# MCU.net
KiCad netlist of a schematic drawn in Altium Designer
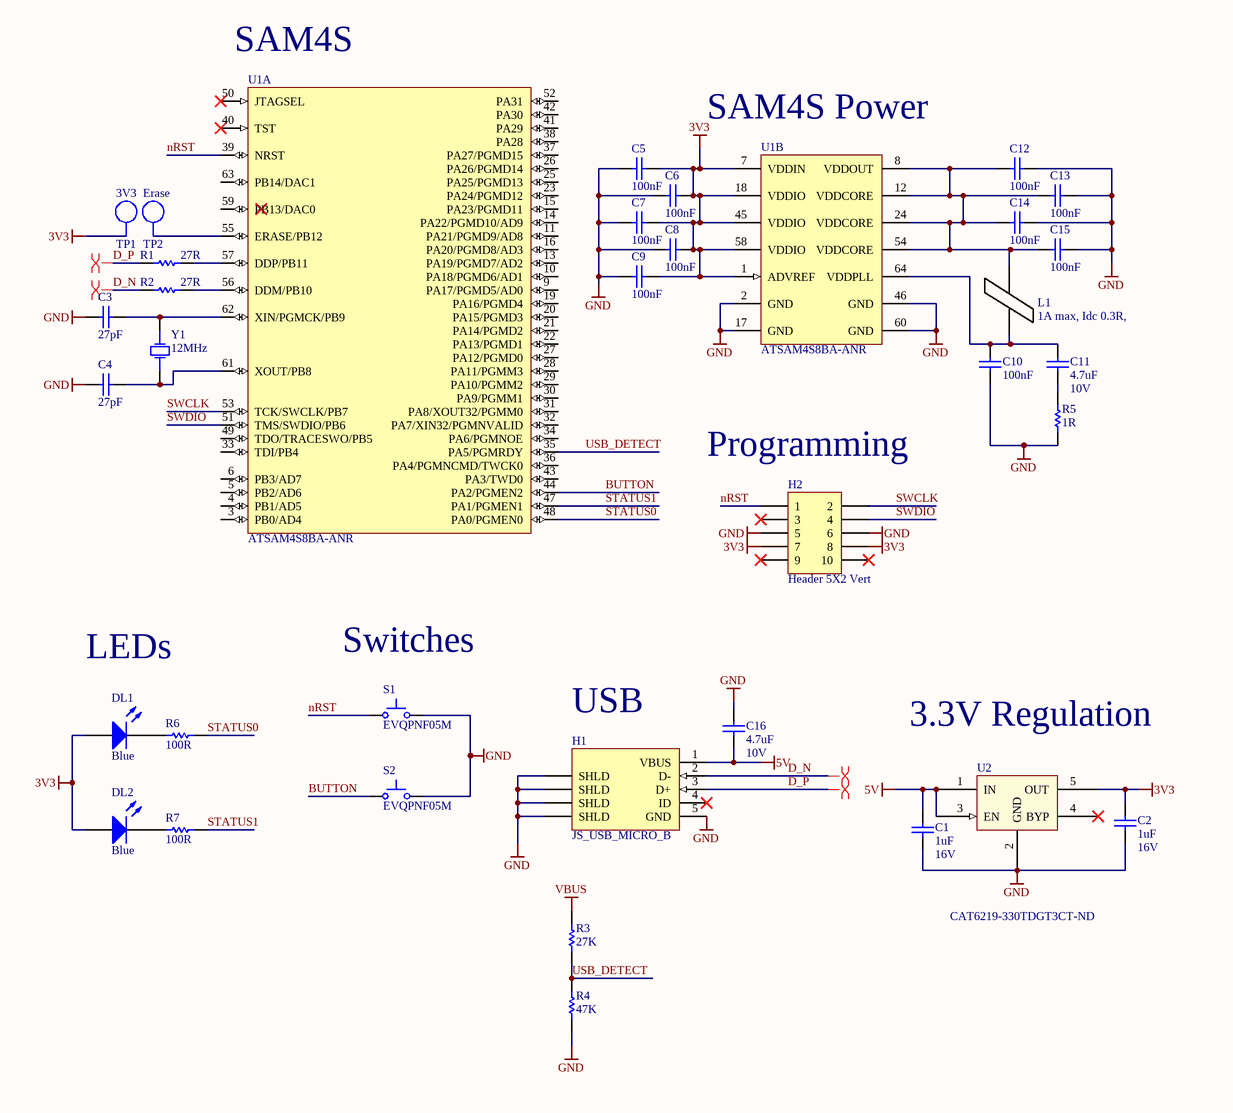
[diagram p0: MCU.SchDoc]

(export (version "E")
  (design (tool "Eeschema 10.0.6"))
  (components
    (comp (ref "C1")
      (value "1uF")
      (footprint "CAPC1608L")
      (description "CAP CER 1uF Y5V -20% +80% 16V 0603")
      (fields (field (name "MAX VOLTAGE") "16V"))
      (libsource (lib "ECE AD19Components_19V1") (part "CC_1uF_0603"))
    )
    (comp (ref "C2")
      (value "1uF")
      (footprint "CAPC1608L")
      (description "CAP CER 1uF Y5V -20% +80% 16V 0603")
      (fields (field (name "MAX VOLTAGE") "16V"))
      (libsource (lib "ECE AD19Components_19V1") (part "CC_1uF_0603"))
    )
    (comp (ref "C3")
      (value "27pF")
      (footprint "CAPC1608L")
      (description "CAP CER 27pF NPO/COG +-5% 50V 0603")
      (libsource (lib "ECE AD19Components_19V1") (part "CC_27pF_0603"))
    )
    (comp (ref "C4")
      (value "27pF")
      (footprint "CAPC1608L")
      (description "CAP CER 27pF NPO/COG +-5% 50V 0603")
      (libsource (lib "ECE AD19Components_19V1") (part "CC_27pF_0603"))
    )
    (comp (ref "C5")
      (value "100nF")
      (footprint "CAPC1608L")
      (description "CAP CER 100nF X7R +-10% 50V 0603")
      (libsource (lib "ECE AD19Components_19V1") (part "CC_100nF_0603"))
    )
    (comp (ref "C6")
      (value "100nF")
      (footprint "CAPC1608L")
      (description "CAP CER 100nF X7R +-10% 50V 0603")
      (libsource (lib "ECE AD19Components_19V1") (part "CC_100nF_0603"))
    )
    (comp (ref "C7")
      (value "100nF")
      (footprint "CAPC1608L")
      (description "CAP CER 100nF X7R +-10% 50V 0603")
      (libsource (lib "ECE AD19Components_19V1") (part "CC_100nF_0603"))
    )
    (comp (ref "C8")
      (value "100nF")
      (footprint "CAPC1608L")
      (description "CAP CER 100nF X7R +-10% 50V 0603")
      (libsource (lib "ECE AD19Components_19V1") (part "CC_100nF_0603"))
    )
    (comp (ref "C9")
      (value "100nF")
      (footprint "CAPC1608L")
      (description "CAP CER 100nF X7R +-10% 50V 0603")
      (libsource (lib "ECE AD19Components_19V1") (part "CC_100nF_0603"))
    )
    (comp (ref "C10")
      (value "100nF")
      (footprint "CAPC1608L")
      (description "CAP CER 100nF X7R +-10% 50V 0603")
      (libsource (lib "ECE AD19Components_19V1") (part "CC_100nF_0603"))
    )
    (comp (ref "C11")
      (value "4.7uF")
      (footprint "CAPC1608N")
      (description "CAP CER 4.7uF X5R +-20%  10V 0603")
      (fields (field (name "MAX VOLTAGE") "10V"))
      (libsource (lib "ECE AD19Components_19V1") (part "CC_4.7uF_0603"))
    )
    (comp (ref "C12")
      (value "100nF")
      (footprint "CAPC1608L")
      (description "CAP CER 100nF X7R +-10% 50V 0603")
      (libsource (lib "ECE AD19Components_19V1") (part "CC_100nF_0603"))
    )
    (comp (ref "C13")
      (value "100nF")
      (footprint "CAPC1608L")
      (description "CAP CER 100nF X7R +-10% 50V 0603")
      (libsource (lib "ECE AD19Components_19V1") (part "CC_100nF_0603"))
    )
    (comp (ref "C14")
      (value "100nF")
      (footprint "CAPC1608L")
      (description "CAP CER 100nF X7R +-10% 50V 0603")
      (libsource (lib "ECE AD19Components_19V1") (part "CC_100nF_0603"))
    )
    (comp (ref "C15")
      (value "100nF")
      (footprint "CAPC1608L")
      (description "CAP CER 100nF X7R +-10% 50V 0603")
      (libsource (lib "ECE AD19Components_19V1") (part "CC_100nF_0603"))
    )
    (comp (ref "C16")
      (value "4.7uF")
      (footprint "CAPC1608N")
      (description "CAP CER 4.7uF X5R +-20%  10V 0603")
      (fields (field (name "MAX VOLTAGE") "10V"))
      (libsource (lib "ECE AD19Components_19V1") (part "CC_4.7uF_0603"))
    )
    (comp (ref "DL1")
      (value "Blue")
      (footprint "WL-SMCW0603")
      (description "LED Blue 270mcd 0603 SMD")
      (fields
        (field (name "MANUFACTURER") "WURTH ELEKTRONIK")
        (field (name "MANUFACTURER PART NUMBER") "150060BS75000")
        (field (name "LED COLOUR") "Blue")
      )
      (libsource (lib "ECE AD19Components_19V1") (part "DL_150060BS75000"))
    )
    (comp (ref "DL2")
      (value "Blue")
      (footprint "WL-SMCW0603")
      (description "LED Blue 270mcd 0603 SMD")
      (fields
        (field (name "MANUFACTURER") "WURTH ELEKTRONIK")
        (field (name "MANUFACTURER PART NUMBER") "150060BS75000")
        (field (name "LED COLOUR") "Blue")
      )
      (libsource (lib "ECE AD19Components_19V1") (part "DL_150060BS75000"))
    )
    (comp (ref "H1")
      (value "JS_USB_MICRO_B")
      (footprint "FCI_USB_10118194-0001LF")
      (description "CONN USB MICRO B RECPT SMT R/A")
      (fields (field (name "MANUFACTURER") "FCI") (field (name "MANUFACTURER PART NUMBER") "10118194-0001LF"))
      (libsource (lib "ECE AD19Components_19V1") (part "JS_USB_MICRO_B_SMT"))
    )
    (comp (ref "H2")
      (value "Header 5X2 Vert")
      (footprint "IDC2.54-V10D")
      (description "IDC Header, 2,54mm, 10-Pin, Vert")
      (libsource (lib "ECE AD19Components_19V1") (part "JA_HDR_IDC_5X2_VERT"))
    )
    (comp (ref "L1")
      (value "1A max, Idc 0.3R,")
      (footprint "INDC3216L")
      (description "Ferrite Bead, Rdc 0.3R, Z100MHZ 600R, Imax 1A, SMD 1206")
      (fields
        (field (name "MANUFACTURER") "FAIR-RITE")
        (field (name "MANUFACTURER PART NUMBER") "2512066017Y1")
      )
      (libsource (lib "ECE AD19Components_19V1") (part "IN_Ferrite-Bead"))
    )
    (comp (ref "R1")
      (value "27R")
      (footprint "RESC3216L")
      (description "RES 27R OHM 1/4W 5% 1206 SMD")
      (libsource (lib "ECE AD19Components_19V1") (part "RT_27R"))
    )
    (comp (ref "R2")
      (value "27R")
      (footprint "RESC3216L")
      (description "RES 27R OHM 1/4W 5% 1206 SMD")
      (libsource (lib "ECE AD19Components_19V1") (part "RT_27R"))
    )
    (comp (ref "R3")
      (value "27K")
      (footprint "RESC1608L")
      (description "RES 27K OHM 1/10W 5% 0603 SMD")
      (libsource (lib "ECE AD19Components_19V1") (part "RS_27K"))
    )
    (comp (ref "R4")
      (value "47K")
      (footprint "RESC1608L")
      (description "RES 27K OHM 1/10W 5% 0603 SMD")
      (libsource (lib "ECE AD19Components_19V1") (part "RS_27K"))
    )
    (comp (ref "R5")
      (value "1R")
      (footprint "RESC3216L")
      (description "RES 1R OHM 1/4W 5% 1206 SMD")
      (libsource (lib "ECE AD19Components_19V1") (part "RT_1R"))
    )
    (comp (ref "R6")
      (value "100R")
      (footprint "RESC3216L")
      (description "RES 100R OHM 1/4W 5% 1206 SMD")
      (libsource (lib "ECE AD19Components_19V1") (part "RT_100R"))
    )
    (comp (ref "R7")
      (value "100R")
      (footprint "RESC3216L")
      (description "RES 100R OHM 1/4W 5% 1206 SMD")
      (libsource (lib "ECE AD19Components_19V1") (part "RT_100R"))
    )
    (comp (ref "S1")
      (value "EVQPNF05M")
      (footprint "EVQPNF05M")
      (description "Panasonic 6 x 3.5mm SMD Light Touch Switch Type SMD")
      (fields (field (name "MANUFACTURER") "Panasonic"))
      (libsource (lib "ECE AD19Components_19V1") (part "WS_EVQPNF05M"))
    )
    (comp (ref "S2")
      (value "EVQPNF05M")
      (footprint "EVQPNF05M")
      (description "Panasonic 6 x 3.5mm SMD Light Touch Switch Type SMD")
      (fields (field (name "MANUFACTURER") "Panasonic"))
      (libsource (lib "ECE AD19Components_19V1") (part "WS_EVQPNF05M"))
    )
    (comp (ref "TP1")
      (value "3V3")
      (footprint "TP_1206")
      (description "Test-Point 3.3x1.6x2.1mm SMD")
      (fields
        (field (name "MANUFACTURER") "Harwin Inc")
        (field (name "MANUFACTURER PART NUMBER") "S1751-46R")
      )
      (libsource (lib "ECE AD19Components_19V1") (part "TP_1206"))
    )
    (comp (ref "TP2")
      (value "Erase")
      (footprint "TP_1206")
      (description "Test-Point 3.3x1.6x2.1mm SMD")
      (fields
        (field (name "MANUFACTURER") "Harwin Inc")
        (field (name "MANUFACTURER PART NUMBER") "S1751-46R")
      )
      (libsource (lib "ECE AD19Components_19V1") (part "TP_1206"))
    )
    (comp (ref "U1")
      (value "ATSAM4S8BA-ANR")
      (footprint "LQFP64_L")
      (description "IC MCU 32BIT 512KB FLASH 64LQFP")
      (fields (field (name "MANUFACTURER") "Atmel"))
      (libsource (lib "ECE AD19Components_19V1") (part "SE_ATSAM4S16BA-MU"))
    )
    (comp (ref "U2")
      (value "CAT6219-330TDGT3")
      (footprint "SOT95P280X145-5N")
      (description "IC REG LIN 3.3V 500MA TSOT23-5")
      (fields
        (field (name "BASE PART NUMBER") "CAT6219")
        (field (name "SUPPLIER PART NUMBER") "CAT6219-330TDGT3CT-ND")
      )
      (libsource (lib "ENCE461AD19_19V2") (part "SV_CAT6219-330TDGT3"))
    )
    (comp (ref "Y1")
      (value "12MHz")
      (footprint "6.0X3.5-4")
      (description "CRYSTAL 12MHZ 18PF 6X3.5mm SMD")
      (fields
        (field (name "MANUFACTURER") "CTS-Frequency Controls")
        (field (name "MANUFACTURER PART NUMBER") "406C35D12M00000")
        (field (name "FREQUENCY") "12MHz")
      )
      (libsource (lib "ECE AD19Components_19V1") (part "XT_CRYSTAL_12MHz_18pF"))
    )
  )
  (nets
    (net (code "1") (name "/BUTTON") (class "Default")
      (node (ref "S2") (pin "1") (pintype "passive"))
      (node (ref "U1") (pin "44") (pinfunction "PA2/PGMEN2_44") (pintype "bidirectional"))
    )
    (net (code "2") (name "/D_N") (class "Default")
      (node (ref "H1") (pin "2") (pinfunction "D-_2") (pintype "input"))
      (node (ref "R2") (pin "1") (pinfunction "1_1") (pintype "passive"))
    )
    (net (code "3") (name "/D_P") (class "Default")
      (node (ref "H1") (pin "3") (pinfunction "D+_3") (pintype "input"))
      (node (ref "R1") (pin "1") (pinfunction "1_1") (pintype "passive"))
    )
    (net (code "4") (name "/STATUS0") (class "Default")
      (node (ref "R6") (pin "2") (pinfunction "2_2") (pintype "passive"))
      (node (ref "U1") (pin "48") (pinfunction "PA0/PGMEN0_48") (pintype "bidirectional"))
    )
    (net (code "5") (name "/STATUS1") (class "Default")
      (node (ref "R7") (pin "2") (pinfunction "2_2") (pintype "passive"))
      (node (ref "U1") (pin "47") (pinfunction "PA1/PGMEN1_47") (pintype "bidirectional"))
    )
    (net (code "6") (name "/SWCLK") (class "Default")
      (node (ref "H2") (pin "2") (pinfunction "2_2") (pintype "passive"))
      (node (ref "U1") (pin "53") (pinfunction "TCK/SWCLK/PB7_53") (pintype "bidirectional"))
    )
    (net (code "7") (name "/SWDIO") (class "Default")
      (node (ref "H2") (pin "4") (pinfunction "4_4") (pintype "passive"))
      (node (ref "U1") (pin "51") (pinfunction "TMS/SWDIO/PB6_51") (pintype "bidirectional"))
    )
    (net (code "8") (name "/USB_DETECT") (class "Default")
      (node (ref "R3") (pin "1") (pinfunction "1_1") (pintype "passive"))
      (node (ref "R4") (pin "2") (pinfunction "2_2") (pintype "passive"))
      (node (ref "U1") (pin "35") (pinfunction "PA5/PGMRDY_35") (pintype "bidirectional"))
    )
    (net (code "9") (name "/nRST") (class "Default")
      (node (ref "H2") (pin "1") (pinfunction "1_1") (pintype "passive"))
      (node (ref "S1") (pin "1") (pintype "passive"))
      (node (ref "U1") (pin "39") (pinfunction "NRST_39") (pintype "bidirectional"))
    )
    (net (code "10") (name "3V3") (class "Default")
      (node (ref "C2") (pin "2") (pinfunction "2_2") (pintype "passive"))
      (node (ref "C5") (pin "2") (pinfunction "2_2") (pintype "passive"))
      (node (ref "C6") (pin "2") (pinfunction "2_2") (pintype "passive"))
      (node (ref "C7") (pin "2") (pinfunction "2_2") (pintype "passive"))
      (node (ref "C8") (pin "2") (pinfunction "2_2") (pintype "passive"))
      (node (ref "C9") (pin "2") (pinfunction "2_2") (pintype "passive"))
      (node (ref "DL1") (pin "2") (pinfunction "A_2") (pintype "passive"))
      (node (ref "DL2") (pin "2") (pinfunction "A_2") (pintype "passive"))
      (node (ref "H2") (pin "7") (pinfunction "7_7") (pintype "passive"))
      (node (ref "H2") (pin "8") (pinfunction "8_8") (pintype "passive"))
      (node (ref "TP1") (pin "1") (pinfunction "1_1") (pintype "passive"))
      (node (ref "U1") (pin "1") (pinfunction "ADVREF_1") (pintype "input"))
      (node (ref "U1") (pin "18") (pinfunction "VDDIO_18") (pintype "power_in"))
      (node (ref "U1") (pin "45") (pinfunction "VDDIO_45") (pintype "power_in"))
      (node (ref "U1") (pin "58") (pinfunction "VDDIO_58") (pintype "power_in"))
      (node (ref "U1") (pin "7") (pinfunction "VDDIN_7") (pintype "power_in"))
      (node (ref "U2") (pin "5") (pinfunction "OUT_5") (pintype "power_in"))
    )
    (net (code "11") (name "5V") (class "Default")
      (node (ref "C1") (pin "2") (pinfunction "2_2") (pintype "passive"))
      (node (ref "C16") (pin "1") (pinfunction "1_1") (pintype "passive"))
      (node (ref "H1") (pin "1") (pinfunction "VBUS_1") (pintype "power_in"))
      (node (ref "U2") (pin "1") (pinfunction "IN_1") (pintype "power_in"))
      (node (ref "U2") (pin "3") (pinfunction "EN_3") (pintype "input"))
    )
    (net (code "12") (name "GND") (class "Default")
      (node (ref "C1") (pin "1") (pinfunction "1_1") (pintype "passive"))
      (node (ref "C10") (pin "1") (pinfunction "1_1") (pintype "passive"))
      (node (ref "C12") (pin "2") (pinfunction "2_2") (pintype "passive"))
      (node (ref "C13") (pin "2") (pinfunction "2_2") (pintype "passive"))
      (node (ref "C14") (pin "2") (pinfunction "2_2") (pintype "passive"))
      (node (ref "C15") (pin "2") (pinfunction "2_2") (pintype "passive"))
      (node (ref "C16") (pin "2") (pinfunction "2_2") (pintype "passive"))
      (node (ref "C2") (pin "1") (pinfunction "1_1") (pintype "passive"))
      (node (ref "C3") (pin "1") (pinfunction "1_1") (pintype "passive"))
      (node (ref "C4") (pin "1") (pinfunction "1_1") (pintype "passive"))
      (node (ref "C5") (pin "1") (pinfunction "1_1") (pintype "passive"))
      (node (ref "C6") (pin "1") (pinfunction "1_1") (pintype "passive"))
      (node (ref "C7") (pin "1") (pinfunction "1_1") (pintype "passive"))
      (node (ref "C8") (pin "1") (pinfunction "1_1") (pintype "passive"))
      (node (ref "C9") (pin "1") (pinfunction "1_1") (pintype "passive"))
      (node (ref "H1") (pin "5") (pinfunction "GND_5") (pintype "passive"))
      (node (ref "H1") (pin "6") (pinfunction "SHLD_6") (pintype "passive"))
      (node (ref "H2") (pin "5") (pinfunction "5_5") (pintype "passive"))
      (node (ref "H2") (pin "6") (pinfunction "6_6") (pintype "passive"))
      (node (ref "R4") (pin "1") (pinfunction "1_1") (pintype "passive"))
      (node (ref "R5") (pin "1") (pinfunction "1_1") (pintype "passive"))
      (node (ref "S1") (pin "2") (pintype "passive"))
      (node (ref "S2") (pin "2") (pintype "passive"))
      (node (ref "U1") (pin "17") (pinfunction "GND_17") (pintype "power_in"))
      (node (ref "U1") (pin "2") (pinfunction "GND_2") (pintype "power_in"))
      (node (ref "U1") (pin "46") (pinfunction "GND_46") (pintype "power_in"))
      (node (ref "U1") (pin "60") (pinfunction "GND_60") (pintype "power_in"))
      (node (ref "U2") (pin "2") (pinfunction "GND_2") (pintype "power_in"))
    )
    (net (code "13") (name "Net-(C11-Pad1)") (class "Default")
      (node (ref "C11") (pin "1") (pinfunction "1_1") (pintype "passive"))
      (node (ref "R5") (pin "2") (pinfunction "2_2") (pintype "passive"))
    )
    (net (code "14") (name "Net-(DL1-K)") (class "Default")
      (node (ref "DL1") (pin "1") (pinfunction "K_1") (pintype "passive"))
      (node (ref "R6") (pin "1") (pinfunction "1_1") (pintype "passive"))
    )
    (net (code "15") (name "Net-(DL2-K)") (class "Default")
      (node (ref "DL2") (pin "1") (pinfunction "K_1") (pintype "passive"))
      (node (ref "R7") (pin "1") (pinfunction "1_1") (pintype "passive"))
    )
    (net (code "16") (name "Net-(U1A-DDM{slash}PB10)") (class "Default")
      (node (ref "R2") (pin "2") (pinfunction "2_2") (pintype "passive"))
      (node (ref "U1") (pin "56") (pinfunction "DDM/PB10_56") (pintype "bidirectional"))
    )
    (net (code "17") (name "Net-(U1A-DDP{slash}PB11)") (class "Default")
      (node (ref "R1") (pin "2") (pinfunction "2_2") (pintype "passive"))
      (node (ref "U1") (pin "57") (pinfunction "DDP/PB11_57") (pintype "bidirectional"))
    )
    (net (code "18") (name "Net-(U1A-ERASE{slash}PB12)") (class "Default")
      (node (ref "TP2") (pin "1") (pinfunction "1_1") (pintype "passive"))
      (node (ref "U1") (pin "55") (pinfunction "ERASE/PB12_55") (pintype "bidirectional"))
    )
    (net (code "19") (name "Net-(U1A-XIN{slash}PGMCK{slash}PB9)") (class "Default")
      (node (ref "C3") (pin "2") (pinfunction "2_2") (pintype "passive"))
      (node (ref "U1") (pin "62") (pinfunction "XIN/PGMCK/PB9_62") (pintype "bidirectional"))
      (node (ref "Y1") (pin "3") (pinfunction "OSC2_3") (pintype "passive"))
    )
    (net (code "20") (name "Net-(U1A-XOUT{slash}PB8)") (class "Default")
      (node (ref "C4") (pin "2") (pinfunction "2_2") (pintype "passive"))
      (node (ref "U1") (pin "61") (pinfunction "XOUT/PB8_61") (pintype "bidirectional"))
      (node (ref "Y1") (pin "1") (pinfunction "OSC1_1") (pintype "passive"))
    )
    (net (code "21") (name "Net-(U1B-VDDOUT)") (class "Default")
      (node (ref "C12") (pin "1") (pinfunction "1_1") (pintype "passive"))
      (node (ref "C13") (pin "1") (pinfunction "1_1") (pintype "passive"))
      (node (ref "C14") (pin "1") (pinfunction "1_1") (pintype "passive"))
      (node (ref "C15") (pin "1") (pinfunction "1_1") (pintype "passive"))
      (node (ref "L1") (pin "2") (pinfunction "2_2") (pintype "passive"))
      (node (ref "U1") (pin "12") (pinfunction "VDDCORE_12") (pintype "power_in"))
      (node (ref "U1") (pin "24") (pinfunction "VDDCORE_24") (pintype "power_in"))
      (node (ref "U1") (pin "54") (pinfunction "VDDCORE_54") (pintype "power_in"))
      (node (ref "U1") (pin "8") (pinfunction "VDDOUT_8") (pintype "power_in"))
    )
    (net (code "22") (name "Net-(U1B-VDDPLL)") (class "Default")
      (node (ref "C10") (pin "2") (pinfunction "2_2") (pintype "passive"))
      (node (ref "C11") (pin "2") (pinfunction "2_2") (pintype "passive"))
      (node (ref "L1") (pin "1") (pinfunction "1_1") (pintype "passive"))
      (node (ref "U1") (pin "64") (pinfunction "VDDPLL_64") (pintype "power_in"))
    )
    (net (code "23") (name "VBUS") (class "Default")
      (node (ref "R3") (pin "2") (pinfunction "2_2") (pintype "passive"))
    )
    (net (code "24") (name "unconnected-(H1-ID-Pad4)") (class "Default")
      (node (ref "H1") (pin "4") (pinfunction "ID_4") (pintype "power_in+no_connect"))
    )
    (net (code "25") (name "unconnected-(H2-Pad3)") (class "Default")
      (node (ref "H2") (pin "3") (pinfunction "3_3") (pintype "passive+no_connect"))
    )
    (net (code "26") (name "unconnected-(H2-Pad9)") (class "Default")
      (node (ref "H2") (pin "9") (pinfunction "9_9") (pintype "passive+no_connect"))
    )
    (net (code "27") (name "unconnected-(H2-Pad10)") (class "Default")
      (node (ref "H2") (pin "10") (pinfunction "10_10") (pintype "passive+no_connect"))
    )
    (net (code "28") (name "unconnected-(U1A-JTAGSEL-Pad50)") (class "Default")
      (node (ref "U1") (pin "50") (pinfunction "JTAGSEL_50") (pintype "input+no_connect"))
    )
    (net (code "29") (name "unconnected-(U1A-PA3{slash}TWD0-Pad43)") (class "Default")
      (node (ref "U1") (pin "43") (pinfunction "PA3/TWD0_43") (pintype "bidirectional"))
    )
    (net (code "30") (name "unconnected-(U1A-PA4{slash}PGMNCMD{slash}TWCK0-Pad36)") (class "Default")
      (node (ref "U1") (pin "36") (pinfunction "PA4/PGMNCMD/TWCK0_36") (pintype "bidirectional"))
    )
    (net (code "31") (name "unconnected-(U1A-PA6{slash}PGMNOE-Pad34)") (class "Default")
      (node (ref "U1") (pin "34") (pinfunction "PA6/PGMNOE_34") (pintype "bidirectional"))
    )
    (net (code "32") (name "unconnected-(U1A-PA7{slash}XIN32{slash}PGMNVALID-Pad32)") (class "Default")
      (node (ref "U1") (pin "32") (pinfunction "PA7/XIN32/PGMNVALID_32") (pintype "bidirectional"))
    )
    (net (code "33") (name "unconnected-(U1A-PA8{slash}XOUT32{slash}PGMM0-Pad31)") (class "Default")
      (node (ref "U1") (pin "31") (pinfunction "PA8/XOUT32/PGMM0_31") (pintype "bidirectional"))
    )
    (net (code "34") (name "unconnected-(U1A-PA9{slash}PGMM1-Pad30)") (class "Default")
      (node (ref "U1") (pin "30") (pinfunction "PA9/PGMM1_30") (pintype "bidirectional"))
    )
    (net (code "35") (name "unconnected-(U1A-PA10{slash}PGMM2-Pad29)") (class "Default")
      (node (ref "U1") (pin "29") (pinfunction "PA10/PGMM2_29") (pintype "bidirectional"))
    )
    (net (code "36") (name "unconnected-(U1A-PA11{slash}PGMM3-Pad28)") (class "Default")
      (node (ref "U1") (pin "28") (pinfunction "PA11/PGMM3_28") (pintype "bidirectional"))
    )
    (net (code "37") (name "unconnected-(U1A-PA12{slash}PGMD0-Pad27)") (class "Default")
      (node (ref "U1") (pin "27") (pinfunction "PA12/PGMD0_27") (pintype "bidirectional"))
    )
    (net (code "38") (name "unconnected-(U1A-PA13{slash}PGMD1-Pad22)") (class "Default")
      (node (ref "U1") (pin "22") (pinfunction "PA13/PGMD1_22") (pintype "bidirectional"))
    )
    (net (code "39") (name "unconnected-(U1A-PA14{slash}PGMD2-Pad21)") (class "Default")
      (node (ref "U1") (pin "21") (pinfunction "PA14/PGMD2_21") (pintype "bidirectional"))
    )
    (net (code "40") (name "unconnected-(U1A-PA15{slash}PGMD3-Pad20)") (class "Default")
      (node (ref "U1") (pin "20") (pinfunction "PA15/PGMD3_20") (pintype "bidirectional"))
    )
    (net (code "41") (name "unconnected-(U1A-PA16{slash}PGMD4-Pad19)") (class "Default")
      (node (ref "U1") (pin "19") (pinfunction "PA16/PGMD4_19") (pintype "bidirectional"))
    )
    (net (code "42") (name "unconnected-(U1A-PA17{slash}PGMD5{slash}AD0-Pad9)") (class "Default")
      (node (ref "U1") (pin "9") (pinfunction "PA17/PGMD5/AD0_9") (pintype "bidirectional"))
    )
    (net (code "43") (name "unconnected-(U1A-PA18{slash}PGMD6{slash}AD1-Pad10)") (class "Default")
      (node (ref "U1") (pin "10") (pinfunction "PA18/PGMD6/AD1_10") (pintype "bidirectional"))
    )
    (net (code "44") (name "unconnected-(U1A-PA19{slash}PGMD7{slash}AD2-Pad13)") (class "Default")
      (node (ref "U1") (pin "13") (pinfunction "PA19/PGMD7/AD2_13") (pintype "bidirectional"))
    )
    (net (code "45") (name "unconnected-(U1A-PA20{slash}PGMD8{slash}AD3-Pad16)") (class "Default")
      (node (ref "U1") (pin "16") (pinfunction "PA20/PGMD8/AD3_16") (pintype "bidirectional"))
    )
    (net (code "46") (name "unconnected-(U1A-PA21{slash}PGMD9{slash}AD8-Pad11)") (class "Default")
      (node (ref "U1") (pin "11") (pinfunction "PA21/PGMD9/AD8_11") (pintype "bidirectional"))
    )
    (net (code "47") (name "unconnected-(U1A-PA22{slash}PGMD10{slash}AD9-Pad14)") (class "Default")
      (node (ref "U1") (pin "14") (pinfunction "PA22/PGMD10/AD9_14") (pintype "bidirectional"))
    )
    (net (code "48") (name "unconnected-(U1A-PA23{slash}PGMD11-Pad15)") (class "Default")
      (node (ref "U1") (pin "15") (pinfunction "PA23/PGMD11_15") (pintype "bidirectional"))
    )
    (net (code "49") (name "unconnected-(U1A-PA24{slash}PGMD12-Pad23)") (class "Default")
      (node (ref "U1") (pin "23") (pinfunction "PA24/PGMD12_23") (pintype "bidirectional"))
    )
    (net (code "50") (name "unconnected-(U1A-PA25{slash}PGMD13-Pad25)") (class "Default")
      (node (ref "U1") (pin "25") (pinfunction "PA25/PGMD13_25") (pintype "bidirectional"))
    )
    (net (code "51") (name "unconnected-(U1A-PA26{slash}PGMD14-Pad26)") (class "Default")
      (node (ref "U1") (pin "26") (pinfunction "PA26/PGMD14_26") (pintype "bidirectional"))
    )
    (net (code "52") (name "unconnected-(U1A-PA27{slash}PGMD15-Pad37)") (class "Default")
      (node (ref "U1") (pin "37") (pinfunction "PA27/PGMD15_37") (pintype "bidirectional"))
    )
    (net (code "53") (name "unconnected-(U1A-PA28-Pad38)") (class "Default")
      (node (ref "U1") (pin "38") (pinfunction "PA28_38") (pintype "bidirectional"))
    )
    (net (code "54") (name "unconnected-(U1A-PA29-Pad41)") (class "Default")
      (node (ref "U1") (pin "41") (pinfunction "PA29_41") (pintype "bidirectional"))
    )
    (net (code "55") (name "unconnected-(U1A-PA30-Pad42)") (class "Default")
      (node (ref "U1") (pin "42") (pinfunction "PA30_42") (pintype "bidirectional"))
    )
    (net (code "56") (name "unconnected-(U1A-PA31-Pad52)") (class "Default")
      (node (ref "U1") (pin "52") (pinfunction "PA31_52") (pintype "bidirectional"))
    )
    (net (code "57") (name "unconnected-(U1A-PB0{slash}AD4-Pad3)") (class "Default")
      (node (ref "U1") (pin "3") (pinfunction "PB0/AD4_3") (pintype "bidirectional"))
    )
    (net (code "58") (name "unconnected-(U1A-PB1{slash}AD5-Pad4)") (class "Default")
      (node (ref "U1") (pin "4") (pinfunction "PB1/AD5_4") (pintype "bidirectional"))
    )
    (net (code "59") (name "unconnected-(U1A-PB2{slash}AD6-Pad5)") (class "Default")
      (node (ref "U1") (pin "5") (pinfunction "PB2/AD6_5") (pintype "bidirectional"))
    )
    (net (code "60") (name "unconnected-(U1A-PB3{slash}AD7-Pad6)") (class "Default")
      (node (ref "U1") (pin "6") (pinfunction "PB3/AD7_6") (pintype "bidirectional"))
    )
    (net (code "61") (name "unconnected-(U1A-PB13{slash}DAC0-Pad59)") (class "Default")
      (node (ref "U1") (pin "59") (pinfunction "PB13/DAC0_59") (pintype "bidirectional"))
    )
    (net (code "62") (name "unconnected-(U1A-PB14{slash}DAC1-Pad63)") (class "Default")
      (node (ref "U1") (pin "63") (pinfunction "PB14/DAC1_63") (pintype "bidirectional"))
    )
    (net (code "63") (name "unconnected-(U1A-TDI{slash}PB4-Pad33)") (class "Default")
      (node (ref "U1") (pin "33") (pinfunction "TDI/PB4_33") (pintype "bidirectional"))
    )
    (net (code "64") (name "unconnected-(U1A-TDO{slash}TRACESWO{slash}PB5-Pad49)") (class "Default")
      (node (ref "U1") (pin "49") (pinfunction "TDO/TRACESWO/PB5_49") (pintype "bidirectional"))
    )
    (net (code "65") (name "unconnected-(U1A-TST-Pad40)") (class "Default")
      (node (ref "U1") (pin "40") (pinfunction "TST_40") (pintype "input+no_connect"))
    )
    (net (code "66") (name "unconnected-(U2-BYP-Pad4)") (class "Default")
      (node (ref "U2") (pin "4") (pinfunction "BYP_4") (pintype "passive+no_connect"))
    )
  )
)
